# stm32_core.net
KiCad netlist of a schematic drawn in Altium Designer
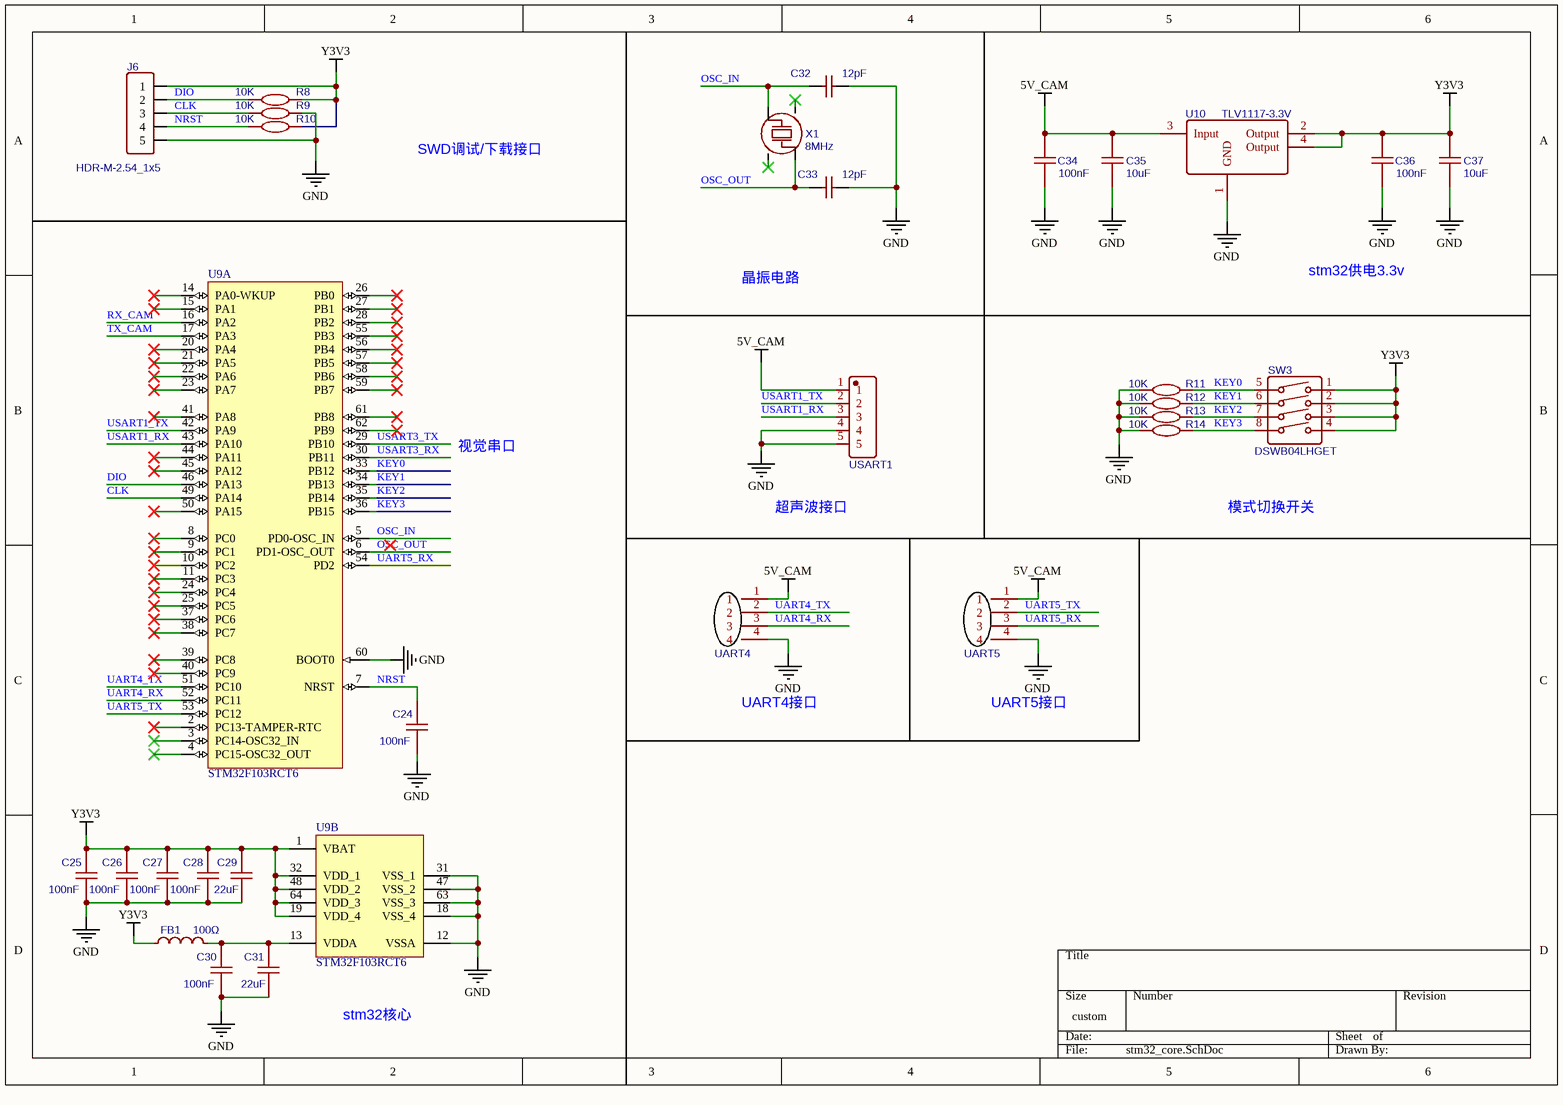
[diagram p0: stm32_core.SchDoc]

(export (version "E")
  (design (tool "Eeschema 10.0.6"))
  (components
    (comp (ref "C24")
      (value "100nF")
      (footprint "C0402")
      (fields
        (field (name "BOM_SUPPLIER PART") "C386075")
        (field (name "BOM_MANUFACTURER PART") "TMK105B7104KVHF")
        (field (name "CONTRIBUTOR") "LCSC")
      )
      (libsource (lib "altium-import") (part "root_0_100nF_"))
    )
    (comp (ref "C25")
      (value "100nF")
      (footprint "C0402")
      (fields
        (field (name "BOM_SUPPLIER PART") "C386075")
        (field (name "BOM_MANUFACTURER PART") "TMK105B7104KVHF")
        (field (name "CONTRIBUTOR") "LCSC")
      )
      (libsource (lib "altium-import") (part "root_0_100nF_"))
    )
    (comp (ref "C26")
      (value "100nF")
      (footprint "C0402")
      (fields
        (field (name "BOM_SUPPLIER PART") "C386075")
        (field (name "BOM_MANUFACTURER PART") "TMK105B7104KVHF")
        (field (name "CONTRIBUTOR") "LCSC")
      )
      (libsource (lib "altium-import") (part "root_0_100nF_"))
    )
    (comp (ref "C27")
      (value "100nF")
      (footprint "C0402")
      (fields
        (field (name "BOM_SUPPLIER PART") "C386075")
        (field (name "BOM_MANUFACTURER PART") "TMK105B7104KVHF")
        (field (name "CONTRIBUTOR") "LCSC")
      )
      (libsource (lib "altium-import") (part "root_0_100nF_"))
    )
    (comp (ref "C28")
      (value "100nF")
      (footprint "C0402")
      (fields
        (field (name "BOM_SUPPLIER PART") "C386075")
        (field (name "BOM_MANUFACTURER PART") "TMK105B7104KVHF")
        (field (name "CONTRIBUTOR") "LCSC")
      )
      (libsource (lib "altium-import") (part "root_0_100nF_"))
    )
    (comp (ref "C29")
      (value "22uF")
      (footprint "C0603")
      (fields
        (field (name "BOM_SUPPLIER PART") "C337440")
        (field (name "BOM_MANUFACTURER PART") "LDK107BBJ226MA-T")
        (field (name "CONTRIBUTOR") "LCSC")
      )
      (libsource (lib "altium-import") (part "root_1_22uF_"))
    )
    (comp (ref "C30")
      (value "100nF")
      (footprint "C0402")
      (fields
        (field (name "BOM_SUPPLIER PART") "C386075")
        (field (name "BOM_MANUFACTURER PART") "TMK105B7104KVHF")
        (field (name "CONTRIBUTOR") "LCSC")
      )
      (libsource (lib "altium-import") (part "root_0_100nF_"))
    )
    (comp (ref "C31")
      (value "22uF")
      (footprint "C0603")
      (fields
        (field (name "BOM_SUPPLIER PART") "C337440")
        (field (name "BOM_MANUFACTURER PART") "LDK107BBJ226MA-T")
        (field (name "CONTRIBUTOR") "LCSC")
      )
      (libsource (lib "altium-import") (part "root_1_22uF_"))
    )
    (comp (ref "C32")
      (value "12pF")
      (footprint "C0402")
      (fields
        (field (name "BOM_MANUFACTURER PART") "UMK105CG120JV-F")
        (field (name "BOM_SUPPLIER PART") "C92842")
      )
      (libsource (lib "altium-import") (part "root_2_12pF_"))
    )
    (comp (ref "C33")
      (value "12pF")
      (footprint "C0402")
      (fields
        (field (name "BOM_MANUFACTURER PART") "UMK105CG120JV-F")
        (field (name "BOM_SUPPLIER PART") "C92842")
      )
      (libsource (lib "altium-import") (part "root_2_12pF_"))
    )
    (comp (ref "C34")
      (value "100nF")
      (footprint "C0402")
      (fields
        (field (name "BOM_SUPPLIER PART") "C386075")
        (field (name "BOM_MANUFACTURER PART") "TMK105B7104KVHF")
        (field (name "CONTRIBUTOR") "LCSC")
      )
      (libsource (lib "altium-import") (part "root_0_100nF_"))
    )
    (comp (ref "C35")
      (value "10uF")
      (footprint "C0805")
      (fields
        (field (name "BOM_SUPPLIER PART") "C386085")
        (field (name "BOM_MANUFACTURER PART") "TMK212BBJ106KG-T")
        (field (name "CONTRIBUTOR") "LCSC")
      )
      (libsource (lib "altium-import") (part "root_0_10uF_"))
    )
    (comp (ref "C36")
      (value "100nF")
      (footprint "C0402")
      (fields
        (field (name "BOM_SUPPLIER PART") "C386075")
        (field (name "BOM_MANUFACTURER PART") "TMK105B7104KVHF")
        (field (name "CONTRIBUTOR") "LCSC")
      )
      (libsource (lib "altium-import") (part "root_0_100nF_"))
    )
    (comp (ref "C37")
      (value "10uF")
      (footprint "C0805")
      (fields
        (field (name "BOM_SUPPLIER PART") "C386085")
        (field (name "BOM_MANUFACTURER PART") "TMK212BBJ106KG-T")
        (field (name "CONTRIBUTOR") "LCSC")
      )
      (libsource (lib "altium-import") (part "root_0_10uF_"))
    )
    (comp (ref "FB1")
      (value "100Ω")
      (footprint "L0603")
      (fields
        (field (name "BOM_MANUFACTURER PART") "MPZ1608D101BTA00")
        (field (name "BOM_SUPPLIER PART") "C87554")
      )
      (libsource (lib "altium-import") (part "root_0_100Ω_"))
    )
    (comp (ref "J6")
      (value "HDR-M-2.54_1x5")
      (footprint "HDR-M-2.54_1X5")
      (fields (field (name "BOM_SUPPLIER PART") "C358687") (field (name "CONTRIBUTOR") "LCEDA_Lib"))
      (libsource (lib "altium-import") (part "root_0_HDR-M-2.54_1x5_"))
    )
    (comp (ref "R8")
      (value "10K")
      (footprint "R0402")
      (fields
        (field (name "BOM_SUPPLIER PART") "C144807")
        (field (name "BOM_MANUFACTURER PART") "AC0402FR-0710KL")
        (field (name "CONTRIBUTOR") "LCSC")
      )
      (libsource (lib "altium-import") (part "root_0_10K_"))
    )
    (comp (ref "R9")
      (value "10K")
      (footprint "R0402")
      (fields
        (field (name "BOM_SUPPLIER PART") "C144807")
        (field (name "BOM_MANUFACTURER PART") "AC0402FR-0710KL")
        (field (name "CONTRIBUTOR") "LCSC")
      )
      (libsource (lib "altium-import") (part "root_0_10K_"))
    )
    (comp (ref "R10")
      (value "10K")
      (footprint "R0402")
      (fields
        (field (name "BOM_SUPPLIER PART") "C144807")
        (field (name "BOM_MANUFACTURER PART") "AC0402FR-0710KL")
        (field (name "CONTRIBUTOR") "LCSC")
      )
      (libsource (lib "altium-import") (part "root_0_10K_"))
    )
    (comp (ref "R11")
      (value "10K")
      (footprint "R0402")
      (fields
        (field (name "BOM_SUPPLIER PART") "C144807")
        (field (name "BOM_MANUFACTURER PART") "AC0402FR-0710KL")
        (field (name "CONTRIBUTOR") "LCSC")
      )
      (libsource (lib "altium-import") (part "root_0_10K_"))
    )
    (comp (ref "R12")
      (value "10K")
      (footprint "R0402")
      (fields
        (field (name "BOM_SUPPLIER PART") "C144807")
        (field (name "BOM_MANUFACTURER PART") "AC0402FR-0710KL")
        (field (name "CONTRIBUTOR") "LCSC")
      )
      (libsource (lib "altium-import") (part "root_0_10K_"))
    )
    (comp (ref "R13")
      (value "10K")
      (footprint "R0402")
      (fields
        (field (name "BOM_SUPPLIER PART") "C144807")
        (field (name "BOM_MANUFACTURER PART") "AC0402FR-0710KL")
        (field (name "CONTRIBUTOR") "LCSC")
      )
      (libsource (lib "altium-import") (part "root_0_10K_"))
    )
    (comp (ref "R14")
      (value "10K")
      (footprint "R0402")
      (fields
        (field (name "BOM_SUPPLIER PART") "C144807")
        (field (name "BOM_MANUFACTURER PART") "AC0402FR-0710KL")
        (field (name "CONTRIBUTOR") "LCSC")
      )
      (libsource (lib "altium-import") (part "root_0_10K_"))
    )
    (comp (ref "SW3")
      (value "DSWB04LHGET")
      (footprint "SW-TH_DSWB04LHGET")
      (fields (field (name "BOM_SUPPLIER PART") "C99418") (field (name "CONTRIBUTOR") "LCSC"))
      (libsource (lib "altium-import") (part "root_3_DSWB04LHGET_"))
    )
    (comp (ref "U9")
      (value "STM32F103RCT6")
      (footprint "STM-LQFP64_N")
      (libsource (lib "STMicroelectronics STM32 F1") (part "STM32F103RCT6"))
    )
    (comp (ref "U10")
      (value "TLV1117-3.3V")
      (footprint "SOT-223-4_L6.5-W3.5-P2.30-LS7.0-BR")
      (fields
        (field (name "BOM_MANUFACTURER PART") "TLV1117-33IDCYR")
        (field (name "BOM_SUPPLIER PART") "C37359")
      )
      (libsource (lib "altium-import") (part "root_0_TLV1117-3.3V_"))
    )
    (comp (ref "UART4")
      (value "XH-4A")
      (footprint "CONN-TH_4P-P2.50_XH-4A")
      (fields (field (name "BOM_SUPPLIER PART") "C37815"))
      (libsource (lib "altium-import") (part "root_0_XH-4A_"))
    )
    (comp (ref "UART5")
      (value "XH-4A")
      (footprint "CONN-TH_4P-P2.50_XH-4A")
      (fields (field (name "BOM_SUPPLIER PART") "C37815"))
      (libsource (lib "altium-import") (part "root_0_XH-4A_"))
    )
    (comp (ref "USART1")
      (value "XH-5A")
      (footprint "CONN-TH_5P-P2.50_XH-5A_C2318")
      (fields (field (name "BOM_SUPPLIER PART") "C2318"))
      (libsource (lib "altium-import") (part "root_0_XH-5A_"))
    )
    (comp (ref "X1")
      (value "8MHz")
      (footprint "OSC-SMD_4P-L3.2-W2.5-BL")
      (fields
        (field (name "BOM_SUPPLIER PART") "C400090")
        (field (name "BOM_MANUFACTURER PART") "TAXM8M4RDBCCT2T")
        (field (name "CONTRIBUTOR") "LCSC")
      )
      (libsource (lib "altium-import") (part "root_1_8MHz_"))
    )
  )
  (nets
    (net (code "1") (name "/CLK") (class "Default")
      (node (ref "J6") (pin "3") (pinfunction "3_3") (pintype "passive"))
      (node (ref "R9") (pin "1") (pinfunction "1_1") (pintype "passive"))
      (node (ref "U9") (pin "49") (pinfunction "PA14_49") (pintype "bidirectional"))
    )
    (net (code "2") (name "/DIO") (class "Default")
      (node (ref "J6") (pin "2") (pinfunction "2_2") (pintype "passive"))
      (node (ref "R8") (pin "1") (pinfunction "1_1") (pintype "passive"))
      (node (ref "U9") (pin "46") (pinfunction "PA13_46") (pintype "bidirectional"))
    )
    (net (code "3") (name "/KEY0") (class "Default")
      (node (ref "R11") (pin "2") (pinfunction "2_2") (pintype "passive"))
      (node (ref "SW3") (pin "5") (pinfunction "5_5") (pintype "passive"))
      (node (ref "U9") (pin "33") (pinfunction "PB12_33") (pintype "bidirectional"))
    )
    (net (code "4") (name "/KEY1") (class "Default")
      (node (ref "R12") (pin "2") (pinfunction "2_2") (pintype "passive"))
      (node (ref "SW3") (pin "6") (pinfunction "6_6") (pintype "passive"))
      (node (ref "U9") (pin "34") (pinfunction "PB13_34") (pintype "bidirectional"))
    )
    (net (code "5") (name "/KEY2") (class "Default")
      (node (ref "R13") (pin "2") (pinfunction "2_2") (pintype "passive"))
      (node (ref "SW3") (pin "7") (pinfunction "7_7") (pintype "passive"))
      (node (ref "U9") (pin "35") (pinfunction "PB14_35") (pintype "bidirectional"))
    )
    (net (code "6") (name "/KEY3") (class "Default")
      (node (ref "R14") (pin "2") (pinfunction "2_2") (pintype "passive"))
      (node (ref "SW3") (pin "8") (pinfunction "8_8") (pintype "passive"))
      (node (ref "U9") (pin "36") (pinfunction "PB15_36") (pintype "bidirectional"))
    )
    (net (code "7") (name "/NRST") (class "Default")
      (node (ref "C24") (pin "2") (pinfunction "2_2") (pintype "passive"))
      (node (ref "J6") (pin "4") (pinfunction "4_4") (pintype "passive"))
      (node (ref "R10") (pin "1") (pinfunction "1_1") (pintype "passive"))
      (node (ref "U9") (pin "7") (pinfunction "NRST_7") (pintype "bidirectional"))
    )
    (net (code "8") (name "/OSC_IN") (class "Default")
      (node (ref "C32") (pin "2") (pinfunction "2_2") (pintype "passive"))
      (node (ref "U9") (pin "5") (pinfunction "PD0-OSC_IN_5") (pintype "bidirectional"))
      (node (ref "X1") (pin "3") (pinfunction "3_3") (pintype "passive"))
    )
    (net (code "9") (name "/OSC_OUT") (class "Default")
      (node (ref "C33") (pin "2") (pinfunction "2_2") (pintype "passive"))
      (node (ref "U9") (pin "6") (pinfunction "PD1-OSC_OUT_6") (pintype "bidirectional"))
      (node (ref "X1") (pin "1") (pinfunction "1_1") (pintype "passive"))
    )
    (net (code "10") (name "/RX_CAM") (class "Default")
      (node (ref "U9") (pin "16") (pinfunction "PA2_16") (pintype "bidirectional"))
    )
    (net (code "11") (name "/TX_CAM") (class "Default")
      (node (ref "U9") (pin "17") (pinfunction "PA3_17") (pintype "bidirectional"))
    )
    (net (code "12") (name "/UART4_RX") (class "Default")
      (node (ref "U9") (pin "52") (pinfunction "PC11_52") (pintype "bidirectional"))
      (node (ref "UART4") (pin "3") (pinfunction "3_3") (pintype "passive"))
    )
    (net (code "13") (name "/UART4_TX") (class "Default")
      (node (ref "U9") (pin "51") (pinfunction "PC10_51") (pintype "bidirectional"))
      (node (ref "UART4") (pin "2") (pinfunction "2_2") (pintype "passive"))
    )
    (net (code "14") (name "/UART5_RX") (class "Default")
      (node (ref "U9") (pin "54") (pinfunction "PD2_54") (pintype "bidirectional"))
      (node (ref "UART5") (pin "3") (pinfunction "3_3") (pintype "passive"))
    )
    (net (code "15") (name "/UART5_TX") (class "Default")
      (node (ref "U9") (pin "53") (pinfunction "PC12_53") (pintype "bidirectional"))
      (node (ref "UART5") (pin "2") (pinfunction "2_2") (pintype "passive"))
    )
    (net (code "16") (name "/USART1_RX") (class "Default")
      (node (ref "U9") (pin "43") (pinfunction "PA10_43") (pintype "bidirectional"))
      (node (ref "USART1") (pin "3") (pinfunction "3_3") (pintype "passive"))
    )
    (net (code "17") (name "/USART1_TX") (class "Default")
      (node (ref "U9") (pin "42") (pinfunction "PA9_42") (pintype "bidirectional"))
      (node (ref "USART1") (pin "2") (pinfunction "2_2") (pintype "passive"))
    )
    (net (code "18") (name "/USART3_RX") (class "Default")
      (node (ref "U9") (pin "30") (pinfunction "PB11_30") (pintype "bidirectional"))
    )
    (net (code "19") (name "/USART3_TX") (class "Default")
      (node (ref "U9") (pin "29") (pinfunction "PB10_29") (pintype "bidirectional"))
    )
    (net (code "20") (name "5V_CAM") (class "Default")
      (node (ref "C34") (pin "2") (pinfunction "2_2") (pintype "passive"))
      (node (ref "C35") (pin "2") (pinfunction "2_2") (pintype "passive"))
      (node (ref "U10") (pin "3") (pinfunction "Input_3") (pintype "passive"))
      (node (ref "UART4") (pin "1") (pinfunction "1_1") (pintype "passive"))
      (node (ref "UART5") (pin "1") (pinfunction "1_1") (pintype "passive"))
      (node (ref "USART1") (pin "1") (pinfunction "1_1") (pintype "passive"))
    )
    (net (code "21") (name "GND") (class "Default")
      (node (ref "C24") (pin "1") (pinfunction "1_1") (pintype "passive"))
      (node (ref "C25") (pin "1") (pinfunction "1_1") (pintype "passive"))
      (node (ref "C26") (pin "1") (pinfunction "1_1") (pintype "passive"))
      (node (ref "C27") (pin "1") (pinfunction "1_1") (pintype "passive"))
      (node (ref "C28") (pin "1") (pinfunction "1_1") (pintype "passive"))
      (node (ref "C29") (pin "1") (pinfunction "1_1") (pintype "passive"))
      (node (ref "C30") (pin "1") (pinfunction "1_1") (pintype "passive"))
      (node (ref "C31") (pin "1") (pinfunction "1_1") (pintype "passive"))
      (node (ref "C32") (pin "1") (pinfunction "1_1") (pintype "passive"))
      (node (ref "C33") (pin "1") (pinfunction "1_1") (pintype "passive"))
      (node (ref "C34") (pin "1") (pinfunction "1_1") (pintype "passive"))
      (node (ref "C35") (pin "1") (pinfunction "1_1") (pintype "passive"))
      (node (ref "C36") (pin "1") (pinfunction "1_1") (pintype "passive"))
      (node (ref "C37") (pin "1") (pinfunction "1_1") (pintype "passive"))
      (node (ref "J6") (pin "5") (pinfunction "5_5") (pintype "passive"))
      (node (ref "R11") (pin "1") (pinfunction "1_1") (pintype "passive"))
      (node (ref "R12") (pin "1") (pinfunction "1_1") (pintype "passive"))
      (node (ref "R13") (pin "1") (pinfunction "1_1") (pintype "passive"))
      (node (ref "R14") (pin "1") (pinfunction "1_1") (pintype "passive"))
      (node (ref "R9") (pin "2") (pinfunction "2_2") (pintype "passive"))
      (node (ref "U10") (pin "1") (pinfunction "GND_1") (pintype "passive"))
      (node (ref "U9") (pin "12") (pinfunction "VSSA_12") (pintype "power_in"))
      (node (ref "U9") (pin "18") (pinfunction "VSS_4_18") (pintype "power_in"))
      (node (ref "U9") (pin "31") (pinfunction "VSS_1_31") (pintype "power_in"))
      (node (ref "U9") (pin "47") (pinfunction "VSS_2_47") (pintype "power_in"))
      (node (ref "U9") (pin "60") (pinfunction "BOOT0_60") (pintype "input"))
      (node (ref "U9") (pin "63") (pinfunction "VSS_3_63") (pintype "power_in"))
      (node (ref "UART4") (pin "4") (pinfunction "4_4") (pintype "passive"))
      (node (ref "UART5") (pin "4") (pinfunction "4_4") (pintype "passive"))
      (node (ref "USART1") (pin "4") (pinfunction "4_4") (pintype "passive"))
      (node (ref "USART1") (pin "5") (pinfunction "5_5") (pintype "passive"))
    )
    (net (code "22") (name "Net-(U9B-VDDA)") (class "Default")
      (node (ref "C30") (pin "2") (pinfunction "2_2") (pintype "passive"))
      (node (ref "C31") (pin "2") (pinfunction "2_2") (pintype "passive"))
      (node (ref "FB1") (pin "2") (pinfunction "2_2") (pintype "passive"))
      (node (ref "U9") (pin "13") (pinfunction "VDDA_13") (pintype "power_in"))
    )
    (net (code "23") (name "Y3V3") (class "Default")
      (node (ref "C25") (pin "2") (pinfunction "2_2") (pintype "passive"))
      (node (ref "C26") (pin "2") (pinfunction "2_2") (pintype "passive"))
      (node (ref "C27") (pin "2") (pinfunction "2_2") (pintype "passive"))
      (node (ref "C28") (pin "2") (pinfunction "2_2") (pintype "passive"))
      (node (ref "C29") (pin "2") (pinfunction "2_2") (pintype "passive"))
      (node (ref "C36") (pin "2") (pinfunction "2_2") (pintype "passive"))
      (node (ref "C37") (pin "2") (pinfunction "2_2") (pintype "passive"))
      (node (ref "FB1") (pin "1") (pinfunction "1_1") (pintype "passive"))
      (node (ref "J6") (pin "1") (pinfunction "1_1") (pintype "passive"))
      (node (ref "R10") (pin "2") (pinfunction "2_2") (pintype "passive"))
      (node (ref "R8") (pin "2") (pinfunction "2_2") (pintype "passive"))
      (node (ref "SW3") (pin "1") (pinfunction "1_1") (pintype "passive"))
      (node (ref "SW3") (pin "2") (pinfunction "2_2") (pintype "passive"))
      (node (ref "SW3") (pin "3") (pinfunction "3_3") (pintype "passive"))
      (node (ref "SW3") (pin "4") (pinfunction "4_4") (pintype "passive"))
      (node (ref "U10") (pin "2") (pinfunction "Output_2") (pintype "passive"))
      (node (ref "U10") (pin "4") (pinfunction "Output_4") (pintype "passive"))
      (node (ref "U9") (pin "1") (pinfunction "VBAT_1") (pintype "power_in"))
      (node (ref "U9") (pin "19") (pinfunction "VDD_4_19") (pintype "power_in"))
      (node (ref "U9") (pin "32") (pinfunction "VDD_1_32") (pintype "power_in"))
      (node (ref "U9") (pin "48") (pinfunction "VDD_2_48") (pintype "power_in"))
      (node (ref "U9") (pin "64") (pinfunction "VDD_3_64") (pintype "power_in"))
    )
    (net (code "24") (name "unconnected-(U9A-PA0-WKUP-Pad14)") (class "Default")
      (node (ref "U9") (pin "14") (pinfunction "PA0-WKUP_14") (pintype "bidirectional+no_connect"))
    )
    (net (code "25") (name "unconnected-(U9A-PA1-Pad15)") (class "Default")
      (node (ref "U9") (pin "15") (pinfunction "PA1_15") (pintype "bidirectional+no_connect"))
    )
    (net (code "26") (name "unconnected-(U9A-PA4-Pad20)") (class "Default")
      (node (ref "U9") (pin "20") (pinfunction "PA4_20") (pintype "bidirectional+no_connect"))
    )
    (net (code "27") (name "unconnected-(U9A-PA5-Pad21)") (class "Default")
      (node (ref "U9") (pin "21") (pinfunction "PA5_21") (pintype "bidirectional+no_connect"))
    )
    (net (code "28") (name "unconnected-(U9A-PA6-Pad22)") (class "Default")
      (node (ref "U9") (pin "22") (pinfunction "PA6_22") (pintype "bidirectional+no_connect"))
    )
    (net (code "29") (name "unconnected-(U9A-PA7-Pad23)") (class "Default")
      (node (ref "U9") (pin "23") (pinfunction "PA7_23") (pintype "bidirectional+no_connect"))
    )
    (net (code "30") (name "unconnected-(U9A-PA8-Pad41)") (class "Default")
      (node (ref "U9") (pin "41") (pinfunction "PA8_41") (pintype "bidirectional+no_connect"))
    )
    (net (code "31") (name "unconnected-(U9A-PA11-Pad44)") (class "Default")
      (node (ref "U9") (pin "44") (pinfunction "PA11_44") (pintype "bidirectional+no_connect"))
    )
    (net (code "32") (name "unconnected-(U9A-PA12-Pad45)") (class "Default")
      (node (ref "U9") (pin "45") (pinfunction "PA12_45") (pintype "bidirectional+no_connect"))
    )
    (net (code "33") (name "unconnected-(U9A-PA15-Pad50)") (class "Default")
      (node (ref "U9") (pin "50") (pinfunction "PA15_50") (pintype "bidirectional+no_connect"))
    )
    (net (code "34") (name "unconnected-(U9A-PB0-Pad26)") (class "Default")
      (node (ref "U9") (pin "26") (pinfunction "PB0_26") (pintype "bidirectional+no_connect"))
    )
    (net (code "35") (name "unconnected-(U9A-PB1-Pad27)") (class "Default")
      (node (ref "U9") (pin "27") (pinfunction "PB1_27") (pintype "bidirectional+no_connect"))
    )
    (net (code "36") (name "unconnected-(U9A-PB2-Pad28)") (class "Default")
      (node (ref "U9") (pin "28") (pinfunction "PB2_28") (pintype "bidirectional+no_connect"))
    )
    (net (code "37") (name "unconnected-(U9A-PB3-Pad55)") (class "Default")
      (node (ref "U9") (pin "55") (pinfunction "PB3_55") (pintype "bidirectional+no_connect"))
    )
    (net (code "38") (name "unconnected-(U9A-PB4-Pad56)") (class "Default")
      (node (ref "U9") (pin "56") (pinfunction "PB4_56") (pintype "bidirectional+no_connect"))
    )
    (net (code "39") (name "unconnected-(U9A-PB5-Pad57)") (class "Default")
      (node (ref "U9") (pin "57") (pinfunction "PB5_57") (pintype "bidirectional+no_connect"))
    )
    (net (code "40") (name "unconnected-(U9A-PB6-Pad58)") (class "Default")
      (node (ref "U9") (pin "58") (pinfunction "PB6_58") (pintype "bidirectional+no_connect"))
    )
    (net (code "41") (name "unconnected-(U9A-PB7-Pad59)") (class "Default")
      (node (ref "U9") (pin "59") (pinfunction "PB7_59") (pintype "bidirectional+no_connect"))
    )
    (net (code "42") (name "unconnected-(U9A-PB8-Pad61)") (class "Default")
      (node (ref "U9") (pin "61") (pinfunction "PB8_61") (pintype "bidirectional+no_connect"))
    )
    (net (code "43") (name "unconnected-(U9A-PB9-Pad62)") (class "Default")
      (node (ref "U9") (pin "62") (pinfunction "PB9_62") (pintype "bidirectional+no_connect"))
    )
    (net (code "44") (name "unconnected-(U9A-PC0-Pad8)") (class "Default")
      (node (ref "U9") (pin "8") (pinfunction "PC0_8") (pintype "bidirectional+no_connect"))
    )
    (net (code "45") (name "unconnected-(U9A-PC1-Pad9)") (class "Default")
      (node (ref "U9") (pin "9") (pinfunction "PC1_9") (pintype "bidirectional+no_connect"))
    )
    (net (code "46") (name "unconnected-(U9A-PC2-Pad10)") (class "Default")
      (node (ref "U9") (pin "10") (pinfunction "PC2_10") (pintype "bidirectional+no_connect"))
    )
    (net (code "47") (name "unconnected-(U9A-PC3-Pad11)") (class "Default")
      (node (ref "U9") (pin "11") (pinfunction "PC3_11") (pintype "bidirectional+no_connect"))
    )
    (net (code "48") (name "unconnected-(U9A-PC4-Pad24)") (class "Default")
      (node (ref "U9") (pin "24") (pinfunction "PC4_24") (pintype "bidirectional+no_connect"))
    )
    (net (code "49") (name "unconnected-(U9A-PC5-Pad25)") (class "Default")
      (node (ref "U9") (pin "25") (pinfunction "PC5_25") (pintype "bidirectional+no_connect"))
    )
    (net (code "50") (name "unconnected-(U9A-PC6-Pad37)") (class "Default")
      (node (ref "U9") (pin "37") (pinfunction "PC6_37") (pintype "bidirectional+no_connect"))
    )
    (net (code "51") (name "unconnected-(U9A-PC7-Pad38)") (class "Default")
      (node (ref "U9") (pin "38") (pinfunction "PC7_38") (pintype "bidirectional+no_connect"))
    )
    (net (code "52") (name "unconnected-(U9A-PC8-Pad39)") (class "Default")
      (node (ref "U9") (pin "39") (pinfunction "PC8_39") (pintype "bidirectional+no_connect"))
    )
    (net (code "53") (name "unconnected-(U9A-PC9-Pad40)") (class "Default")
      (node (ref "U9") (pin "40") (pinfunction "PC9_40") (pintype "bidirectional+no_connect"))
    )
    (net (code "54") (name "unconnected-(U9A-PC13-TAMPER-RTC-Pad2)") (class "Default")
      (node (ref "U9") (pin "2") (pinfunction "PC13-TAMPER-RTC_2") (pintype "bidirectional+no_connect"))
    )
    (net (code "55") (name "unconnected-(U9A-PC14-OSC32_IN-Pad3)") (class "Default")
      (node (ref "U9") (pin "3") (pinfunction "PC14-OSC32_IN_3") (pintype "bidirectional+no_connect"))
    )
    (net (code "56") (name "unconnected-(U9A-PC15-OSC32_OUT-Pad4)") (class "Default")
      (node (ref "U9") (pin "4") (pinfunction "PC15-OSC32_OUT_4") (pintype "bidirectional+no_connect"))
    )
    (net (code "57") (name "unconnected-(X1-Pad2)") (class "Default")
      (node (ref "X1") (pin "2") (pinfunction "2_2") (pintype "passive+no_connect"))
    )
    (net (code "58") (name "unconnected-(X1-Pad4)") (class "Default")
      (node (ref "X1") (pin "4") (pinfunction "4_4") (pintype "passive+no_connect"))
    )
  )
)
